# 09_Misc.net
KiCad netlist of a schematic drawn in Altium Designer
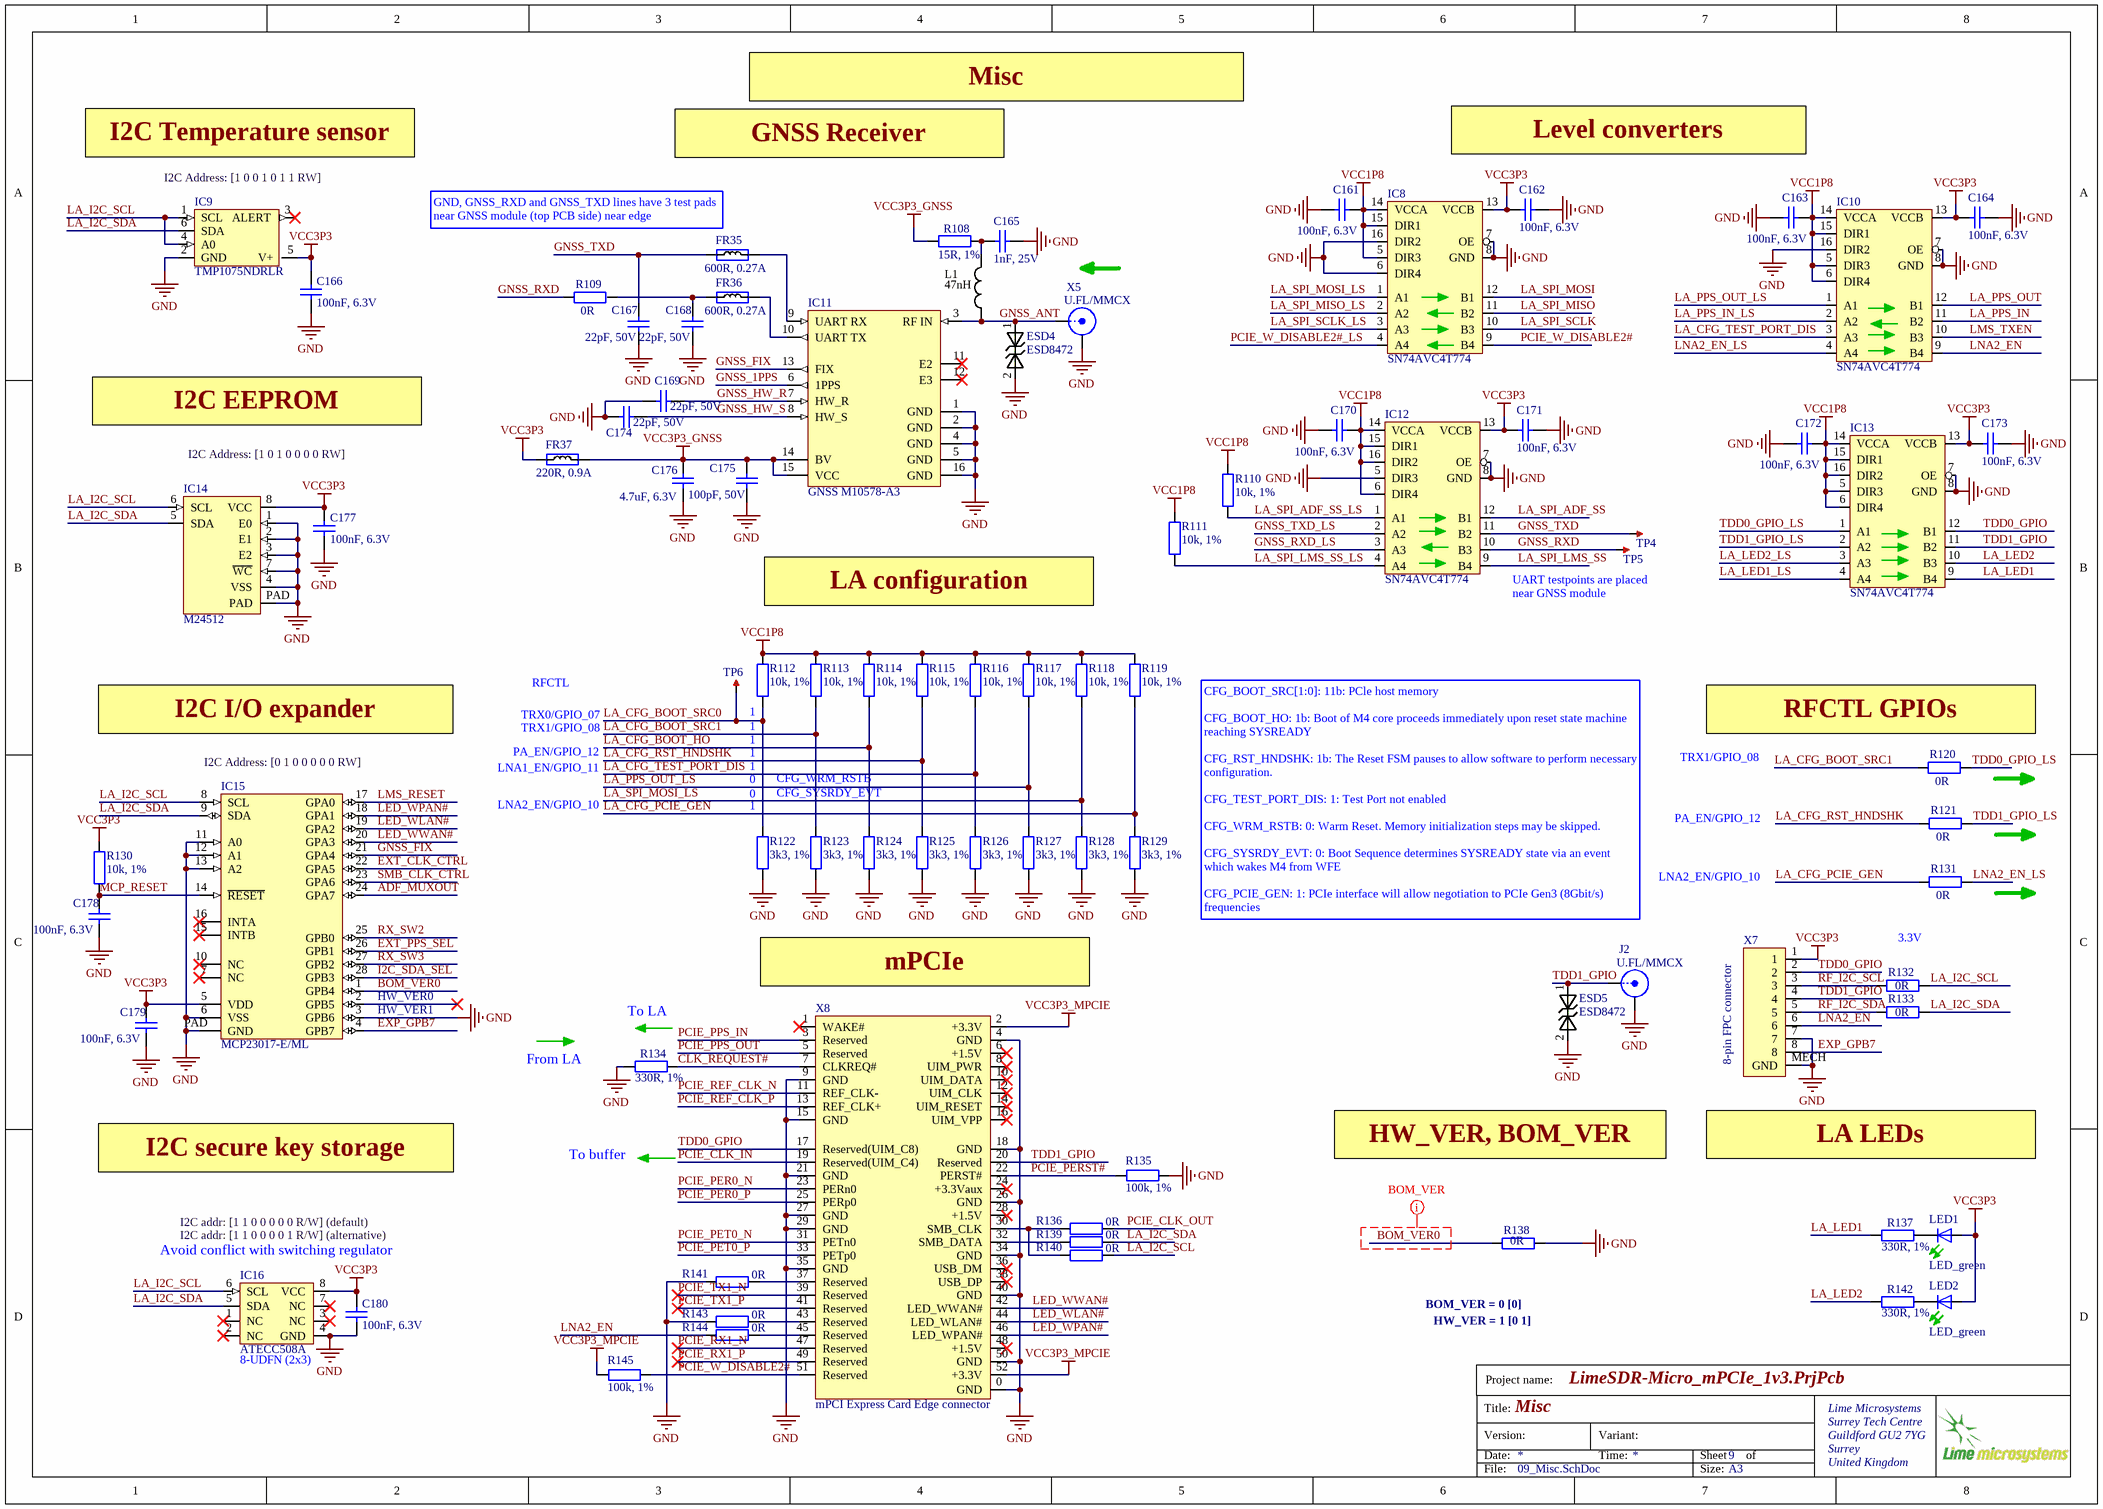
[diagram p0: 09_Misc.SchDoc]

(export (version "E")
  (design (tool "Eeschema 10.0.6"))
  (components
    (comp (ref "C161")
      (value "100nF, 6.3V")
      (footprint "CAP0201")
      (fields (field (name "MANUFACTURER") "Samsung") (field (name "TOLERANCE") "20%"))
      (libsource (lib "LimeMicroAltiumLib_schLib") (part "Cap_0402"))
    )
    (comp (ref "C162")
      (value "100nF, 6.3V")
      (footprint "CAP0201")
      (fields (field (name "MANUFACTURER") "Samsung") (field (name "TOLERANCE") "20%"))
      (libsource (lib "LimeMicroAltiumLib_schLib") (part "Cap_0402"))
    )
    (comp (ref "C163")
      (value "100nF, 6.3V")
      (footprint "CAP0201")
      (fields (field (name "MANUFACTURER") "Samsung") (field (name "TOLERANCE") "20%"))
      (libsource (lib "LimeMicroAltiumLib_schLib") (part "Cap_0402"))
    )
    (comp (ref "C164")
      (value "100nF, 6.3V")
      (footprint "CAP0201")
      (fields (field (name "MANUFACTURER") "Samsung") (field (name "TOLERANCE") "20%"))
      (libsource (lib "LimeMicroAltiumLib_schLib") (part "Cap_0402"))
    )
    (comp (ref "C165")
      (value "1nF, 25V")
      (footprint "CAP0201")
      (fields (field (name "TOLERANCE") "±10%") (field (name "MANUFACTURER") "TDK Corporation"))
      (libsource (lib "LimeMicroAltiumLib_schLib") (part "Cap_0402"))
    )
    (comp (ref "C166")
      (value "100nF, 6.3V")
      (footprint "CAP0201")
      (fields (field (name "MANUFACTURER") "Samsung") (field (name "TOLERANCE") "20%"))
      (libsource (lib "LimeMicroAltiumLib_schLib") (part "Cap_0402"))
    )
    (comp (ref "C167")
      (value "22pF, 50V")
      (footprint "CAP0201")
      (fields
        (field (name "MANUFACTURER") "Murata")
        (field (name "TOLERANCE") "5%")
        (field (name "VOLTAGE") "50V")
      )
      (libsource (lib "LimeMicroAltiumLib_schLib") (part "Cap_0402"))
    )
    (comp (ref "C168")
      (value "22pF, 50V")
      (footprint "CAP0201")
      (fields
        (field (name "MANUFACTURER") "Murata")
        (field (name "TOLERANCE") "5%")
        (field (name "VOLTAGE") "50V")
      )
      (libsource (lib "LimeMicroAltiumLib_schLib") (part "Cap_0402"))
    )
    (comp (ref "C169")
      (value "22pF, 50V")
      (footprint "CAP0201")
      (fields
        (field (name "MANUFACTURER") "Murata")
        (field (name "TOLERANCE") "5%")
        (field (name "VOLTAGE") "50V")
      )
      (libsource (lib "LimeMicroAltiumLib_schLib") (part "Cap_0402"))
    )
    (comp (ref "C170")
      (value "100nF, 6.3V")
      (footprint "CAP0201")
      (fields (field (name "MANUFACTURER") "Samsung") (field (name "TOLERANCE") "20%"))
      (libsource (lib "LimeMicroAltiumLib_schLib") (part "Cap_0402"))
    )
    (comp (ref "C171")
      (value "100nF, 6.3V")
      (footprint "CAP0201")
      (fields (field (name "MANUFACTURER") "Samsung") (field (name "TOLERANCE") "20%"))
      (libsource (lib "LimeMicroAltiumLib_schLib") (part "Cap_0402"))
    )
    (comp (ref "C172")
      (value "100nF, 6.3V")
      (footprint "CAP0201")
      (fields (field (name "MANUFACTURER") "Samsung") (field (name "TOLERANCE") "20%"))
      (libsource (lib "LimeMicroAltiumLib_schLib") (part "Cap_0402"))
    )
    (comp (ref "C173")
      (value "100nF, 6.3V")
      (footprint "CAP0201")
      (fields (field (name "MANUFACTURER") "Samsung") (field (name "TOLERANCE") "20%"))
      (libsource (lib "LimeMicroAltiumLib_schLib") (part "Cap_0402"))
    )
    (comp (ref "C174")
      (value "22pF, 50V")
      (footprint "CAP0201")
      (fields
        (field (name "MANUFACTURER") "Murata")
        (field (name "TOLERANCE") "5%")
        (field (name "VOLTAGE") "50V")
      )
      (libsource (lib "LimeMicroAltiumLib_schLib") (part "Cap_0402"))
    )
    (comp (ref "C175")
      (value "100pF, 50V")
      (footprint "CAP0201")
      (fields
        (field (name "MANUFACTURER") "TDK")
        (field (name "TOLERANCE") "5%")
        (field (name "VOLTAGE") "50V")
      )
      (libsource (lib "LimeMicroAltiumLib_schLib") (part "Cap_0402"))
    )
    (comp (ref "C176")
      (value "4.7uF, 6.3V")
      (footprint "CAP0402")
      (fields
        (field (name "MANUFACTURER") "Murata Electronics North America")
        (field (name "TOLERANCE") "±20%")
      )
      (libsource (lib "LimeMicroAltiumLib_schLib") (part "Cap_0402"))
    )
    (comp (ref "C177")
      (value "100nF, 6.3V")
      (footprint "CAP0201")
      (fields (field (name "MANUFACTURER") "Samsung") (field (name "TOLERANCE") "20%"))
      (libsource (lib "LimeMicroAltiumLib_schLib") (part "Cap_0402"))
    )
    (comp (ref "C178")
      (value "100nF, 6.3V")
      (footprint "CAP0201")
      (fields (field (name "MANUFACTURER") "Samsung") (field (name "TOLERANCE") "20%"))
      (libsource (lib "LimeMicroAltiumLib_schLib") (part "Cap_0402"))
    )
    (comp (ref "C179")
      (value "100nF, 6.3V")
      (footprint "CAP0201")
      (fields (field (name "MANUFACTURER") "Samsung") (field (name "TOLERANCE") "20%"))
      (libsource (lib "LimeMicroAltiumLib_schLib") (part "Cap_0402"))
    )
    (comp (ref "C180")
      (value "100nF, 6.3V")
      (footprint "CAP0201")
      (fields (field (name "MANUFACTURER") "Samsung") (field (name "TOLERANCE") "20%"))
      (libsource (lib "LimeMicroAltiumLib_schLib") (part "Cap_0402"))
    )
    (comp (ref "ESD4")
      (value "ESD8472")
      (footprint "ESD8472_X3DFN2")
      (fields (field (name "MANUFACTURER") "ON Semiconductor"))
      (libsource (lib "LimeMicroAltiumLib_schLib") (part "ESD8472"))
    )
    (comp (ref "ESD5")
      (value "ESD8472")
      (footprint "ESD8472_X3DFN2")
      (fields (field (name "MANUFACTURER") "ON Semiconductor"))
      (libsource (lib "LimeMicroAltiumLib_schLib") (part "ESD8472"))
    )
    (comp (ref "FR35")
      (value "600R, 0.27A")
      (footprint "RES0201")
      (fields (field (name "MANUFACTURER") "Taiyo Yuden"))
      (libsource (lib "LimeMicroAltiumLib_schLib") (part "Ferrite"))
    )
    (comp (ref "FR36")
      (value "600R, 0.27A")
      (footprint "RES0201")
      (fields (field (name "MANUFACTURER") "Taiyo Yuden"))
      (libsource (lib "LimeMicroAltiumLib_schLib") (part "Ferrite"))
    )
    (comp (ref "FR37")
      (value "220R, 0.9A")
      (footprint "RES0402")
      (fields (field (name "MANUFACTURER") "TDK Corporation"))
      (libsource (lib "LimeFPGAboard_schLib") (part "Ferrite"))
    )
    (comp (ref "IC8")
      (value "SN74AVC4T774")
      (footprint "SN74AVC4T774_v1")
      (fields (field (name "MANUFACTURER") "Texas Instruments"))
      (libsource (lib "LimeMicroAltiumLib") (part "SN74AVC4T774"))
    )
    (comp (ref "IC9")
      (value "TMP1075NDRLR")
      (footprint "TMP1075NDRLR_temperature_sensor_SOT563")
      (fields (field (name "MANUFACTURER") "Texas Instruments"))
      (libsource (lib "LimeMicroAltiumLib_schLib_r04") (part "TMP1075NDRLR_temperature_sensor"))
    )
    (comp (ref "IC10")
      (value "SN74AVC4T774")
      (footprint "SN74AVC4T774_v1")
      (fields (field (name "MANUFACTURER") "Texas Instruments"))
      (libsource (lib "LimeMicroAltiumLib") (part "SN74AVC4T774"))
    )
    (comp (ref "IC11")
      (value "GNSS M10578-A3")
      (footprint "M10578-A3_v2")
      (fields (field (name "MANUFACTURER") "Antenova"))
      (libsource (lib "LimeMicroAltiumLib_schLib_r04") (part "M10578-A3_GPS_GNSS"))
    )
    (comp (ref "IC12")
      (value "SN74AVC4T774")
      (footprint "SN74AVC4T774_v1")
      (fields (field (name "MANUFACTURER") "Texas Instruments"))
      (libsource (lib "LimeMicroAltiumLib") (part "SN74AVC4T774"))
    )
    (comp (ref "IC13")
      (value "SN74AVC4T774")
      (footprint "SN74AVC4T774_v1")
      (fields (field (name "MANUFACTURER") "Texas Instruments"))
      (libsource (lib "LimeMicroAltiumLib") (part "SN74AVC4T774"))
    )
    (comp (ref "IC14")
      (value "M24512")
      (footprint "M24128-DFMC6TG")
      (fields (field (name "MANUFACTURER") "STMicroelectronics"))
      (libsource (lib "LimeMicroAltiumLib_schLib") (part "M24128-DFMC6TG"))
    )
    (comp (ref "IC15")
      (value "MCP23017-E/ML")
      (footprint "MCP23017-E/ML_QFN28")
      (fields (field (name "MANUFACTURER") "Microchip"))
      (libsource (lib "LimeMicroAltiumLib") (part "MCP23017-E/ML_I2C_expander"))
    )
    (comp (ref "IC16")
      (value "ATECC508A")
      (footprint "LimeMicroAltiumLib:ATECC508A_UDFN8_v2")
      (fields (field (name "MANUFACTURER") "Microchip"))
      (libsource (lib "LimeMicroAltiumLib_schLib_r01") (part "ATECC508A_authentication_IC"))
    )
    (comp (ref "J2")
      (value "U.FL/MMCX")
      (footprint "MMCX_UFL_conn_u_v2")
      (description "CONN UMC RCPT STR 50 OHM SMD")
      (fields (field (name "MANUFACTURER") "Molex, LLC"))
      (libsource (lib "LimeMicroAltiumLib_schLib") (part "RF_IF_connector"))
    )
    (comp (ref "L1")
      (value "47nH")
      (footprint "RES0402")
      (fields
        (field (name "MANUFACTURER") "COILCRAFT")
        (field (name "MANUFACTURER PART NUMBER") "0402HP-47NXJLU")
      )
      (libsource (lib "LimeMicroAltiumLib_schLib") (part "Inductor_0603"))
    )
    (comp (ref "LED1")
      (value "LED_green")
      (footprint "LED0201")
      (fields (field (name "MANUFACTURER") "Kingbright"))
      (libsource (lib "LimeFPGAboard_schLib") (part "LED_green"))
    )
    (comp (ref "LED2")
      (value "LED_green")
      (footprint "LED0201")
      (fields (field (name "MANUFACTURER") "Kingbright"))
      (libsource (lib "LimeFPGAboard_schLib") (part "LED_green"))
    )
    (comp (ref "R108")
      (value "15R, 1%")
      (footprint "RES0201")
      (fields (field (name "MANUFACTURER") "Yageo") (field (name "TOLERANCE") "1%"))
      (libsource (lib "LimeFPGAboard_schLib") (part "Res_0402"))
    )
    (comp (ref "R109")
      (value "0R")
      (footprint "RES0201")
      (fields (field (name "MANUFACTURER") "Yageo") (field (name "TOLERANCE") "5%"))
      (libsource (lib "LimeFPGAboard_schLib") (part "Res_0402"))
    )
    (comp (ref "R110")
      (value "10k, 1%")
      (footprint "RES0201")
      (fields (field (name "MANUFACTURER") "Yageo") (field (name "TOLERANCE") "1%"))
      (libsource (lib "LimeFPGAboard_schLib") (part "Res_0402"))
    )
    (comp (ref "R111")
      (value "10k, 1%")
      (footprint "RES0201")
      (fields (field (name "MANUFACTURER") "Yageo") (field (name "TOLERANCE") "1%"))
      (libsource (lib "LimeFPGAboard_schLib") (part "Res_0402"))
    )
    (comp (ref "R112")
      (value "10k, 1%")
      (footprint "RES0201")
      (fields (field (name "MANUFACTURER") "Yageo") (field (name "TOLERANCE") "1%"))
      (libsource (lib "LimeFPGAboard_schLib") (part "Res_0402"))
    )
    (comp (ref "R113")
      (value "10k, 1%")
      (footprint "RES0201")
      (fields (field (name "MANUFACTURER") "Yageo") (field (name "TOLERANCE") "1%"))
      (libsource (lib "LimeFPGAboard_schLib") (part "Res_0402"))
    )
    (comp (ref "R114")
      (value "10k, 1%")
      (footprint "RES0201")
      (fields (field (name "MANUFACTURER") "Yageo") (field (name "TOLERANCE") "1%"))
      (libsource (lib "LimeFPGAboard_schLib") (part "Res_0402"))
    )
    (comp (ref "R115")
      (value "10k, 1%")
      (footprint "RES0201")
      (fields (field (name "MANUFACTURER") "Yageo") (field (name "TOLERANCE") "1%"))
      (libsource (lib "LimeFPGAboard_schLib") (part "Res_0402"))
    )
    (comp (ref "R116")
      (value "10k, 1%")
      (footprint "RES0201")
      (fields (field (name "MANUFACTURER") "Yageo") (field (name "TOLERANCE") "1%"))
      (libsource (lib "LimeFPGAboard_schLib") (part "Res_0402"))
    )
    (comp (ref "R117")
      (value "10k, 1%")
      (footprint "RES0201")
      (fields (field (name "MANUFACTURER") "Yageo") (field (name "TOLERANCE") "1%"))
      (libsource (lib "LimeFPGAboard_schLib") (part "Res_0402"))
    )
    (comp (ref "R118")
      (value "10k, 1%")
      (footprint "RES0201")
      (fields (field (name "MANUFACTURER") "Yageo") (field (name "TOLERANCE") "1%"))
      (libsource (lib "LimeFPGAboard_schLib") (part "Res_0402"))
    )
    (comp (ref "R119")
      (value "10k, 1%")
      (footprint "RES0201")
      (fields (field (name "MANUFACTURER") "Yageo") (field (name "TOLERANCE") "1%"))
      (libsource (lib "LimeFPGAboard_schLib") (part "Res_0402"))
    )
    (comp (ref "R120")
      (value "0R")
      (footprint "RES0201")
      (fields (field (name "MANUFACTURER") "Yageo") (field (name "TOLERANCE") "5%"))
      (libsource (lib "LimeFPGAboard_schLib") (part "Res_0402"))
    )
    (comp (ref "R121")
      (value "0R")
      (footprint "RES0201")
      (fields (field (name "MANUFACTURER") "Yageo") (field (name "TOLERANCE") "5%"))
      (libsource (lib "LimeFPGAboard_schLib") (part "Res_0402"))
    )
    (comp (ref "R122")
      (value "3k3, 1%")
      (footprint "RES0201")
      (fields (field (name "MANUFACTURER") "Yageo") (field (name "TOLERANCE") "1%"))
      (libsource (lib "LimeFPGAboard_schLib") (part "Res_0402"))
    )
    (comp (ref "R123")
      (value "3k3, 1%")
      (footprint "RES0201")
      (fields (field (name "MANUFACTURER") "Yageo") (field (name "TOLERANCE") "1%"))
      (libsource (lib "LimeFPGAboard_schLib") (part "Res_0402"))
    )
    (comp (ref "R124")
      (value "3k3, 1%")
      (footprint "RES0201")
      (fields (field (name "MANUFACTURER") "Yageo") (field (name "TOLERANCE") "1%"))
      (libsource (lib "LimeFPGAboard_schLib") (part "Res_0402"))
    )
    (comp (ref "R125")
      (value "3k3, 1%")
      (footprint "RES0201")
      (fields (field (name "MANUFACTURER") "Yageo") (field (name "TOLERANCE") "1%"))
      (libsource (lib "LimeFPGAboard_schLib") (part "Res_0402"))
    )
    (comp (ref "R126")
      (value "3k3, 1%")
      (footprint "RES0201")
      (fields (field (name "MANUFACTURER") "Yageo") (field (name "TOLERANCE") "1%"))
      (libsource (lib "LimeFPGAboard_schLib") (part "Res_0402"))
    )
    (comp (ref "R127")
      (value "3k3, 1%")
      (footprint "RES0201")
      (fields (field (name "MANUFACTURER") "Yageo") (field (name "TOLERANCE") "1%"))
      (libsource (lib "LimeFPGAboard_schLib") (part "Res_0402"))
    )
    (comp (ref "R128")
      (value "3k3, 1%")
      (footprint "RES0201")
      (fields (field (name "MANUFACTURER") "Yageo") (field (name "TOLERANCE") "1%"))
      (libsource (lib "LimeFPGAboard_schLib") (part "Res_0402"))
    )
    (comp (ref "R129")
      (value "3k3, 1%")
      (footprint "RES0201")
      (fields (field (name "MANUFACTURER") "Yageo") (field (name "TOLERANCE") "1%"))
      (libsource (lib "LimeFPGAboard_schLib") (part "Res_0402"))
    )
    (comp (ref "R130")
      (value "10k, 1%")
      (footprint "RES0201")
      (fields (field (name "MANUFACTURER") "Yageo") (field (name "TOLERANCE") "1%"))
      (libsource (lib "LimeFPGAboard_schLib") (part "Res_0402"))
    )
    (comp (ref "R131")
      (value "0R")
      (footprint "RES0201")
      (fields (field (name "MANUFACTURER") "Yageo") (field (name "TOLERANCE") "5%"))
      (libsource (lib "LimeFPGAboard_schLib") (part "Res_0402"))
    )
    (comp (ref "R132")
      (value "0R")
      (footprint "RES0201")
      (fields (field (name "MANUFACTURER") "Yageo") (field (name "TOLERANCE") "5%"))
      (libsource (lib "LimeFPGAboard_schLib") (part "Res_0402"))
    )
    (comp (ref "R133")
      (value "0R")
      (footprint "RES0201")
      (fields (field (name "MANUFACTURER") "Yageo") (field (name "TOLERANCE") "5%"))
      (libsource (lib "LimeFPGAboard_schLib") (part "Res_0402"))
    )
    (comp (ref "R134")
      (value "330R, 1%")
      (footprint "RES0201")
      (fields (field (name "MANUFACTURER") "Vishay Dale") (field (name "TOLERANCE") "1%"))
      (libsource (lib "LimeFPGAboard_schLib") (part "Res_0402"))
    )
    (comp (ref "R135")
      (value "100k, 1%")
      (footprint "RES0201")
      (fields (field (name "MANUFACTURER") "Yageo") (field (name "TOLERANCE") "1%"))
      (libsource (lib "LimeMicroAltiumLib_schLib") (part "Res_0402"))
    )
    (comp (ref "R136")
      (value "0R")
      (footprint "RES0201")
      (fields (field (name "MANUFACTURER") "Yageo") (field (name "TOLERANCE") "5%"))
      (libsource (lib "LimeFPGAboard_schLib") (part "Res_0402"))
    )
    (comp (ref "R137")
      (value "330R, 1%")
      (footprint "RES0201")
      (fields (field (name "MANUFACTURER") "Vishay Dale") (field (name "TOLERANCE") "1%"))
      (libsource (lib "LimeFPGAboard_schLib") (part "Res_0402"))
    )
    (comp (ref "R138")
      (value "0R")
      (footprint "RES0201")
      (fields (field (name "MANUFACTURER") "Yageo") (field (name "TOLERANCE") "5%"))
      (libsource (lib "LimeFPGAboard_schLib") (part "Res_0402"))
    )
    (comp (ref "R139")
      (value "0R")
      (footprint "RES0201")
      (fields (field (name "MANUFACTURER") "Yageo") (field (name "TOLERANCE") "5%"))
      (libsource (lib "LimeFPGAboard_schLib") (part "Res_0402"))
    )
    (comp (ref "R140")
      (value "0R")
      (footprint "RES0201")
      (fields (field (name "MANUFACTURER") "Yageo") (field (name "TOLERANCE") "5%"))
      (libsource (lib "LimeFPGAboard_schLib") (part "Res_0402"))
    )
    (comp (ref "R141")
      (value "0R")
      (footprint "RES0201")
      (fields (field (name "MANUFACTURER") "Yageo") (field (name "TOLERANCE") "5%"))
      (libsource (lib "LimeFPGAboard_schLib") (part "Res_0402"))
    )
    (comp (ref "R142")
      (value "330R, 1%")
      (footprint "RES0201")
      (fields (field (name "MANUFACTURER") "Vishay Dale") (field (name "TOLERANCE") "1%"))
      (libsource (lib "LimeFPGAboard_schLib") (part "Res_0402"))
    )
    (comp (ref "R143")
      (value "0R")
      (footprint "RES0201")
      (fields (field (name "MANUFACTURER") "Yageo") (field (name "TOLERANCE") "5%"))
      (libsource (lib "LimeFPGAboard_schLib") (part "Res_0402"))
    )
    (comp (ref "R144")
      (value "0R")
      (footprint "RES0201")
      (fields (field (name "MANUFACTURER") "Yageo") (field (name "TOLERANCE") "5%"))
      (libsource (lib "LimeFPGAboard_schLib") (part "Res_0402"))
    )
    (comp (ref "R145")
      (value "100k, 1%")
      (footprint "RES0201")
      (fields (field (name "MANUFACTURER") "Yageo") (field (name "TOLERANCE") "1%"))
      (libsource (lib "LimeMicroAltiumLib_schLib") (part "Res_0402"))
    )
    (comp (ref "TP4")
      (value "TESTPOINT_PAD")
      (footprint "TP_PAD_1MM")
      (description "Test Point PCB mount Miniature White")
      (libsource (lib "LimeMicroAltiumLib_schLib_r04") (part "TESTPOINT_PAD"))
    )
    (comp (ref "TP5")
      (value "TESTPOINT_PAD")
      (footprint "TP_PAD_1MM")
      (description "Test Point PCB mount Miniature White")
      (libsource (lib "LimeMicroAltiumLib_schLib_r04") (part "TESTPOINT_PAD"))
    )
    (comp (ref "TP6")
      (value "TESTPOINT_PAD")
      (footprint "TP_PAD_1MM")
      (description "Test Point PCB mount Miniature White")
      (libsource (lib "LimeMicroAltiumLib_schLib_r04") (part "TESTPOINT_PAD"))
    )
    (comp (ref "X5")
      (value "U.FL/MMCX")
      (footprint "MMCX_UFL_conn_u_v2")
      (description "CONN UMC RCPT STR 50 OHM SMD")
      (fields (field (name "MANUFACTURER") "Molex, LLC"))
      (libsource (lib "LimeMicroAltiumLib_schLib") (part "RF_IF_connector"))
    )
    (comp (ref "X7")
      (value "8-pin FPC connector")
      (footprint "503480-0800_8PIN_FPC_CONN")
      (fields (field (name "MANUFACTURER") "Molex"))
      (libsource (lib "LimeMicroAltiumLib_schLib_r04") (part "503480-0800_8PIN_FPC_CONN"))
    )
    (comp (ref "X8")
      (value "mPCI Express Card Edge connector")
      (footprint "PCIe_MiniCard")
      (description "PCIe MiniCard full or half size")
      (libsource (lib "LimeMicroAltiumLib_schLib_r04") (part "PCIe_MiniCard_fingers"))
    )
  )
  (nets
    (net (code "1") (name "/ADF_MUXOUT") (class "Default")
      (node (ref "IC15") (pin "24") (pinfunction "GPA7_24") (pintype "bidirectional"))
    )
    (net (code "2") (name "/BOM_VER0") (class "Default")
      (node (ref "IC15") (pin "1") (pinfunction "GPB4_1") (pintype "bidirectional"))
      (node (ref "R138") (pin "1") (pinfunction "1_1") (pintype "passive"))
    )
    (net (code "3") (name "/CLK_REQUEST#") (class "Default")
      (node (ref "R134") (pin "1") (pinfunction "1_1") (pintype "passive"))
      (node (ref "X8") (pin "7") (pinfunction "CLKREQ#_7") (pintype "passive"))
    )
    (net (code "4") (name "/EXP_GPB7") (class "Default")
      (node (ref "IC15") (pin "4") (pinfunction "GPB7_4") (pintype "bidirectional"))
      (node (ref "X7") (pin "8") (pinfunction "8_8") (pintype "passive"))
    )
    (net (code "5") (name "/EXT_CLK_CTRL") (class "Default")
      (node (ref "IC15") (pin "22") (pinfunction "GPA5_22") (pintype "bidirectional"))
    )
    (net (code "6") (name "/EXT_PPS_SEL") (class "Default")
      (node (ref "IC15") (pin "26") (pinfunction "GPB1_26") (pintype "bidirectional"))
    )
    (net (code "7") (name "/GNSS_1PPS") (class "Default")
      (node (ref "IC11") (pin "6") (pinfunction "1PPS_6") (pintype "output"))
    )
    (net (code "8") (name "/GNSS_ANT") (class "Default")
      (node (ref "ESD4") (pin "1") (pinfunction "1_1") (pintype "passive"))
      (node (ref "IC11") (pin "3") (pinfunction "RF_IN_3") (pintype "input"))
      (node (ref "L1") (pin "1") (pinfunction "1_1") (pintype "passive"))
      (node (ref "X5") (pin "1") (pinfunction "X_1") (pintype "passive"))
    )
    (net (code "9") (name "/GNSS_FIX") (class "Default")
      (node (ref "IC11") (pin "13") (pinfunction "FIX_13") (pintype "output"))
      (node (ref "IC15") (pin "21") (pinfunction "GPA4_21") (pintype "bidirectional"))
    )
    (net (code "10") (name "/GNSS_HW_R") (class "Default")
      (node (ref "C169") (pin "1") (pinfunction "1_1") (pintype "passive"))
      (node (ref "IC11") (pin "7") (pinfunction "HW_R_7") (pintype "input"))
    )
    (net (code "11") (name "/GNSS_HW_S") (class "Default")
      (node (ref "C174") (pin "1") (pinfunction "1_1") (pintype "passive"))
      (node (ref "IC11") (pin "8") (pinfunction "HW_S_8") (pintype "input"))
    )
    (net (code "12") (name "/GNSS_RXD") (class "Default")
      (node (ref "IC12") (pin "10") (pinfunction "B3_10") (pintype "passive"))
      (node (ref "R109") (pin "1") (pinfunction "1_1") (pintype "passive"))
      (node (ref "TP5") (pin "1") (pintype "passive"))
    )
    (net (code "13") (name "/GNSS_RXD_LS") (class "Default")
      (node (ref "IC12") (pin "3") (pinfunction "A3_3") (pintype "passive"))
    )
    (net (code "14") (name "/GNSS_TXD") (class "Default")
      (node (ref "C167") (pin "1") (pinfunction "1_1") (pintype "passive"))
      (node (ref "FR35") (pin "1") (pinfunction "1_1") (pintype "passive"))
      (node (ref "IC12") (pin "11") (pinfunction "B2_11") (pintype "passive"))
      (node (ref "TP4") (pin "1") (pintype "passive"))
    )
    (net (code "15") (name "/GNSS_TXD_LS") (class "Default")
      (node (ref "IC12") (pin "2") (pinfunction "A2_2") (pintype "passive"))
    )
    (net (code "16") (name "/I2C_SDA_SEL") (class "Default")
      (node (ref "IC15") (pin "28") (pinfunction "GPB3_28") (pintype "bidirectional"))
    )
    (net (code "17") (name "/LA_CFG_BOOT_HO") (class "Default")
      (node (ref "R114") (pin "2") (pinfunction "2_2") (pintype "passive"))
      (node (ref "R124") (pin "1") (pinfunction "1_1") (pintype "passive"))
    )
    (net (code "18") (name "/LA_CFG_BOOT_SRC0") (class "Default")
      (node (ref "R112") (pin "2") (pinfunction "2_2") (pintype "passive"))
      (node (ref "R122") (pin "1") (pinfunction "1_1") (pintype "passive"))
      (node (ref "TP6") (pin "1") (pintype "passive"))
    )
    (net (code "19") (name "/LA_CFG_BOOT_SRC1") (class "Default")
      (node (ref "R113") (pin "2") (pinfunction "2_2") (pintype "passive"))
      (node (ref "R120") (pin "1") (pinfunction "1_1") (pintype "passive"))
      (node (ref "R123") (pin "1") (pinfunction "1_1") (pintype "passive"))
    )
    (net (code "20") (name "/LA_CFG_PCIE_GEN") (class "Default")
      (node (ref "R119") (pin "2") (pinfunction "2_2") (pintype "passive"))
      (node (ref "R129") (pin "1") (pinfunction "1_1") (pintype "passive"))
      (node (ref "R131") (pin "1") (pinfunction "1_1") (pintype "passive"))
    )
    (net (code "21") (name "/LA_CFG_RST_HNDSHK") (class "Default")
      (node (ref "R115") (pin "2") (pinfunction "2_2") (pintype "passive"))
      (node (ref "R121") (pin "1") (pinfunction "1_1") (pintype "passive"))
      (node (ref "R125") (pin "1") (pinfunction "1_1") (pintype "passive"))
    )
    (net (code "22") (name "/LA_CFG_TEST_PORT_DIS") (class "Default")
      (node (ref "IC10") (pin "3") (pinfunction "A3_3") (pintype "passive"))
      (node (ref "R116") (pin "2") (pinfunction "2_2") (pintype "passive"))
      (node (ref "R126") (pin "1") (pinfunction "1_1") (pintype "passive"))
    )
    (net (code "23") (name "/LA_I2C_SCL") (class "Default")
      (node (ref "IC14") (pin "6") (pinfunction "SCL_6") (pintype "input"))
      (node (ref "IC15") (pin "8") (pinfunction "SCL_8") (pintype "input"))
      (node (ref "IC16") (pin "6") (pinfunction "SCL_6") (pintype "input"))
      (node (ref "IC9") (pin "1") (pinfunction "SCL_1") (pintype "input"))
      (node (ref "IC9") (pin "4") (pinfunction "A0_4") (pintype "input"))
      (node (ref "R132") (pin "2") (pinfunction "2_2") (pintype "passive"))
      (node (ref "R140") (pin "2") (pinfunction "2_2") (pintype "passive"))
    )
    (net (code "24") (name "/LA_I2C_SDA") (class "Default")
      (node (ref "IC14") (pin "5") (pinfunction "SDA_5") (pintype "bidirectional"))
      (node (ref "IC15") (pin "9") (pinfunction "SDA_9") (pintype "bidirectional"))
      (node (ref "IC16") (pin "5") (pinfunction "SDA_5") (pintype "bidirectional"))
      (node (ref "IC9") (pin "6") (pinfunction "SDA_6") (pintype "bidirectional"))
      (node (ref "R133") (pin "2") (pinfunction "2_2") (pintype "passive"))
      (node (ref "R139") (pin "2") (pinfunction "2_2") (pintype "passive"))
    )
    (net (code "25") (name "/LA_LED1") (class "Default")
      (node (ref "IC13") (pin "9") (pinfunction "B4_9") (pintype "passive"))
      (node (ref "R137") (pin "2") (pinfunction "2_2") (pintype "passive"))
    )
    (net (code "26") (name "/LA_LED1_LS") (class "Default")
      (node (ref "IC13") (pin "4") (pinfunction "A4_4") (pintype "passive"))
    )
    (net (code "27") (name "/LA_LED2") (class "Default")
      (node (ref "IC13") (pin "10") (pinfunction "B3_10") (pintype "passive"))
      (node (ref "R142") (pin "2") (pinfunction "2_2") (pintype "passive"))
    )
    (net (code "28") (name "/LA_LED2_LS") (class "Default")
      (node (ref "IC13") (pin "3") (pinfunction "A3_3") (pintype "passive"))
    )
    (net (code "29") (name "/LA_PPS_IN") (class "Default")
      (node (ref "IC10") (pin "11") (pinfunction "B2_11") (pintype "passive"))
    )
    (net (code "30") (name "/LA_PPS_IN_LS") (class "Default")
      (node (ref "IC10") (pin "2") (pinfunction "A2_2") (pintype "passive"))
    )
    (net (code "31") (name "/LA_PPS_OUT") (class "Default")
      (node (ref "IC10") (pin "12") (pinfunction "B1_12") (pintype "passive"))
    )
    (net (code "32") (name "/LA_PPS_OUT_LS") (class "Default")
      (node (ref "IC10") (pin "1") (pinfunction "A1_1") (pintype "passive"))
      (node (ref "R117") (pin "2") (pinfunction "2_2") (pintype "passive"))
      (node (ref "R127") (pin "1") (pinfunction "1_1") (pintype "passive"))
    )
    (net (code "33") (name "/LA_SPI_ADF_SS") (class "Default")
      (node (ref "IC12") (pin "12") (pinfunction "B1_12") (pintype "passive"))
    )
    (net (code "34") (name "/LA_SPI_ADF_SS_LS") (class "Default")
      (node (ref "IC12") (pin "1") (pinfunction "A1_1") (pintype "passive"))
      (node (ref "R110") (pin "2") (pinfunction "2_2") (pintype "passive"))
    )
    (net (code "35") (name "/LA_SPI_LMS_SS") (class "Default")
      (node (ref "IC12") (pin "9") (pinfunction "B4_9") (pintype "passive"))
    )
    (net (code "36") (name "/LA_SPI_LMS_SS_LS") (class "Default")
      (node (ref "IC12") (pin "4") (pinfunction "A4_4") (pintype "passive"))
      (node (ref "R111") (pin "2") (pinfunction "2_2") (pintype "passive"))
    )
    (net (code "37") (name "/LA_SPI_MISO") (class "Default")
      (node (ref "IC8") (pin "11") (pinfunction "B2_11") (pintype "passive"))
    )
    (net (code "38") (name "/LA_SPI_MISO_LS") (class "Default")
      (node (ref "IC8") (pin "2") (pinfunction "A2_2") (pintype "passive"))
    )
    (net (code "39") (name "/LA_SPI_MOSI") (class "Default")
      (node (ref "IC8") (pin "12") (pinfunction "B1_12") (pintype "passive"))
    )
    (net (code "40") (name "/LA_SPI_MOSI_LS") (class "Default")
      (node (ref "IC8") (pin "1") (pinfunction "A1_1") (pintype "passive"))
      (node (ref "R118") (pin "2") (pinfunction "2_2") (pintype "passive"))
      (node (ref "R128") (pin "1") (pinfunction "1_1") (pintype "passive"))
    )
    (net (code "41") (name "/LA_SPI_SCLK") (class "Default")
      (node (ref "IC8") (pin "10") (pinfunction "B3_10") (pintype "passive"))
    )
    (net (code "42") (name "/LA_SPI_SCLK_LS") (class "Default")
      (node (ref "IC8") (pin "3") (pinfunction "A3_3") (pintype "passive"))
    )
    (net (code "43") (name "/LED_WLAN#") (class "Default")
      (node (ref "IC15") (pin "19") (pinfunction "GPA2_19") (pintype "bidirectional"))
      (node (ref "X8") (pin "44") (pinfunction "LED_WLAN#_44") (pintype "passive"))
    )
    (net (code "44") (name "/LED_WPAN#") (class "Default")
      (node (ref "IC15") (pin "18") (pinfunction "GPA1_18") (pintype "bidirectional"))
      (node (ref "X8") (pin "46") (pinfunction "LED_WPAN#_46") (pintype "passive"))
    )
    (net (code "45") (name "/LED_WWAN#") (class "Default")
      (node (ref "IC15") (pin "20") (pinfunction "GPA3_20") (pintype "bidirectional"))
      (node (ref "X8") (pin "42") (pinfunction "LED_WWAN#_42") (pintype "passive"))
    )
    (net (code "46") (name "/LMS_RESET") (class "Default")
      (node (ref "IC15") (pin "17") (pinfunction "GPA0_17") (pintype "bidirectional"))
    )
    (net (code "47") (name "/LMS_TXEN") (class "Default")
      (node (ref "IC10") (pin "10") (pinfunction "B3_10") (pintype "passive"))
    )
    (net (code "48") (name "/LNA2_EN") (class "Default")
      (node (ref "IC10") (pin "9") (pinfunction "B4_9") (pintype "passive"))
      (node (ref "R144") (pin "1") (pinfunction "1_1") (pintype "passive"))
      (node (ref "X7") (pin "6") (pinfunction "6_6") (pintype "passive"))
    )
    (net (code "49") (name "/LNA2_EN_LS") (class "Default")
      (node (ref "IC10") (pin "4") (pinfunction "A4_4") (pintype "passive"))
      (node (ref "R131") (pin "2") (pinfunction "2_2") (pintype "passive"))
    )
    (net (code "50") (name "/MCP_RESET") (class "Default")
      (node (ref "C178") (pin "1") (pinfunction "1_1") (pintype "passive"))
      (node (ref "IC15") (pin "14") (pinfunction "~{RESET}_14") (pintype "input"))
      (node (ref "R130") (pin "2") (pinfunction "2_2") (pintype "passive"))
    )
    (net (code "51") (name "/PCIE_CLK_IN") (class "Default")
      (node (ref "X8") (pin "19") (pinfunction "Reserved(UIM_C4)_19") (pintype "passive"))
    )
    (net (code "52") (name "/PCIE_CLK_OUT") (class "Default")
      (node (ref "R136") (pin "2") (pinfunction "2_2") (pintype "passive"))
    )
    (net (code "53") (name "/PCIE_PER0_N") (class "Default")
      (node (ref "X8") (pin "23") (pinfunction "PERn0_23") (pintype "passive"))
    )
    (net (code "54") (name "/PCIE_PER0_P") (class "Default")
      (node (ref "X8") (pin "25") (pinfunction "PERp0_25") (pintype "passive"))
    )
    (net (code "55") (name "/PCIE_PERST#") (class "Default")
      (node (ref "R135") (pin "2") (pinfunction "2_2") (pintype "passive"))
      (node (ref "X8") (pin "22") (pinfunction "PERST#_22") (pintype "passive"))
    )
    (net (code "56") (name "/PCIE_PET0_N") (class "Default")
      (node (ref "X8") (pin "31") (pinfunction "PETn0_31") (pintype "passive"))
    )
    (net (code "57") (name "/PCIE_PET0_P") (class "Default")
      (node (ref "X8") (pin "33") (pinfunction "PETp0_33") (pintype "passive"))
    )
    (net (code "58") (name "/PCIE_PPS_IN") (class "Default")
      (node (ref "X8") (pin "3") (pinfunction "Reserved_3") (pintype "passive"))
    )
    (net (code "59") (name "/PCIE_PPS_OUT") (class "Default")
      (node (ref "X8") (pin "5") (pinfunction "Reserved_5") (pintype "passive"))
    )
    (net (code "60") (name "/PCIE_REF_CLK_N") (class "Default")
      (node (ref "X8") (pin "11") (pinfunction "REF_CLK-_11") (pintype "passive"))
    )
    (net (code "61") (name "/PCIE_REF_CLK_P") (class "Default")
      (node (ref "X8") (pin "13") (pinfunction "REF_CLK+_13") (pintype "passive"))
    )
    (net (code "62") (name "/PCIE_RX1_N") (class "Default")
      (node (ref "X8") (pin "47") (pinfunction "Reserved_47") (pintype "passive+no_connect"))
    )
    (net (code "63") (name "/PCIE_RX1_P") (class "Default")
      (node (ref "X8") (pin "49") (pinfunction "Reserved_49") (pintype "passive+no_connect"))
    )
    (net (code "64") (name "/PCIE_TX1_N") (class "Default")
      (node (ref "X8") (pin "39") (pinfunction "Reserved_39") (pintype "passive+no_connect"))
    )
    (net (code "65") (name "/PCIE_TX1_P") (class "Default")
      (node (ref "X8") (pin "41") (pinfunction "Reserved_41") (pintype "passive+no_connect"))
    )
    (net (code "66") (name "/PCIE_W_DISABLE2#") (class "Default")
      (node (ref "IC8") (pin "9") (pinfunction "B4_9") (pintype "passive"))
      (node (ref "R145") (pin "1") (pinfunction "1_1") (pintype "passive"))
      (node (ref "X8") (pin "51") (pinfunction "Reserved_51") (pintype "passive"))
    )
    (net (code "67") (name "/PCIE_W_DISABLE2#_LS") (class "Default")
      (node (ref "IC8") (pin "4") (pinfunction "A4_4") (pintype "passive"))
    )
    (net (code "68") (name "/RF_I2C_SCL") (class "Default")
      (node (ref "R132") (pin "1") (pinfunction "1_1") (pintype "passive"))
      (node (ref "X7") (pin "3") (pinfunction "3_3") (pintype "passive"))
    )
    (net (code "69") (name "/RF_I2C_SDA") (class "Default")
      (node (ref "R133") (pin "1") (pinfunction "1_1") (pintype "passive"))
      (node (ref "X7") (pin "5") (pinfunction "5_5") (pintype "passive"))
    )
    (net (code "70") (name "/RX_SW2") (class "Default")
      (node (ref "IC15") (pin "25") (pinfunction "GPB0_25") (pintype "bidirectional"))
    )
    (net (code "71") (name "/RX_SW3") (class "Default")
      (node (ref "IC15") (pin "27") (pinfunction "GPB2_27") (pintype "bidirectional"))
    )
    (net (code "72") (name "/SMB_CLK_CTRL") (class "Default")
      (node (ref "IC15") (pin "23") (pinfunction "GPA6_23") (pintype "bidirectional"))
    )
    (net (code "73") (name "/TDD0_GPIO") (class "Default")
      (node (ref "IC13") (pin "12") (pinfunction "B1_12") (pintype "passive"))
      (node (ref "X7") (pin "2") (pinfunction "2_2") (pintype "passive"))
      (node (ref "X8") (pin "17") (pinfunction "Reserved(UIM_C8)_17") (pintype "passive"))
    )
    (net (code "74") (name "/TDD0_GPIO_LS") (class "Default")
      (node (ref "IC13") (pin "1") (pinfunction "A1_1") (pintype "passive"))
      (node (ref "R120") (pin "2") (pinfunction "2_2") (pintype "passive"))
    )
    (net (code "75") (name "/TDD1_GPIO") (class "Default")
      (node (ref "ESD5") (pin "1") (pinfunction "1_1") (pintype "passive"))
      (node (ref "IC13") (pin "11") (pinfunction "B2_11") (pintype "passive"))
      (node (ref "J2") (pin "1") (pinfunction "X_1") (pintype "passive"))
      (node (ref "X7") (pin "4") (pinfunction "4_4") (pintype "passive"))
      (node (ref "X8") (pin "20") (pinfunction "Reserved_20") (pintype "passive"))
    )
    (net (code "76") (name "/TDD1_GPIO_LS") (class "Default")
      (node (ref "IC13") (pin "2") (pinfunction "A2_2") (pintype "passive"))
      (node (ref "R121") (pin "2") (pinfunction "2_2") (pintype "passive"))
    )
    (net (code "77") (name "GND") (class "Default")
      (node (ref "C161") (pin "1") (pinfunction "1_1") (pintype "passive"))
      (node (ref "C162") (pin "2") (pinfunction "2_2") (pintype "passive"))
      (node (ref "C163") (pin "1") (pinfunction "1_1") (pintype "passive"))
      (node (ref "C164") (pin "2") (pinfunction "2_2") (pintype "passive"))
      (node (ref "C165") (pin "2") (pinfunction "2_2") (pintype "passive"))
      (node (ref "C166") (pin "2") (pinfunction "2_2") (pintype "passive"))
      (node (ref "C167") (pin "2") (pinfunction "2_2") (pintype "passive"))
      (node (ref "C168") (pin "2") (pinfunction "2_2") (pintype "passive"))
      (node (ref "C169") (pin "2") (pinfunction "2_2") (pintype "passive"))
      (node (ref "C170") (pin "1") (pinfunction "1_1") (pintype "passive"))
      (node (ref "C171") (pin "2") (pinfunction "2_2") (pintype "passive"))
      (node (ref "C172") (pin "1") (pinfunction "1_1") (pintype "passive"))
      (node (ref "C173") (pin "2") (pinfunction "2_2") (pintype "passive"))
      (node (ref "C174") (pin "2") (pinfunction "2_2") (pintype "passive"))
      (node (ref "C175") (pin "1") (pinfunction "1_1") (pintype "passive"))
      (node (ref "C176") (pin "1") (pinfunction "1_1") (pintype "passive"))
      (node (ref "C177") (pin "2") (pinfunction "2_2") (pintype "passive"))
      (node (ref "C178") (pin "2") (pinfunction "2_2") (pintype "passive"))
      (node (ref "C179") (pin "2") (pinfunction "2_2") (pintype "passive"))
      (node (ref "C180") (pin "2") (pinfunction "2_2") (pintype "passive"))
      (node (ref "ESD4") (pin "2") (pinfunction "2_2") (pintype "passive"))
      (node (ref "ESD5") (pin "2") (pinfunction "2_2") (pintype "passive"))
      (node (ref "IC10") (pin "16") (pinfunction "DIR2_16") (pintype "passive"))
      (node (ref "IC10") (pin "7") (pinfunction "OE_7") (pintype "passive"))
      (node (ref "IC10") (pin "8") (pinfunction "GND_8") (pintype "passive"))
      (node (ref "IC11") (pin "1") (pinfunction "GND_1") (pintype "passive"))
      (node (ref "IC11") (pin "16") (pinfunction "GND_16") (pintype "passive"))
      (node (ref "IC11") (pin "2") (pinfunction "GND_2") (pintype "passive"))
      (node (ref "IC11") (pin "4") (pinfunction "GND_4") (pintype "passive"))
      (node (ref "IC11") (pin "5") (pinfunction "GND_5") (pintype "passive"))
      (node (ref "IC12") (pin "5") (pinfunction "DIR3_5") (pintype "passive"))
      (node (ref "IC12") (pin "7") (pinfunction "OE_7") (pintype "passive"))
      (node (ref "IC12") (pin "8") (pinfunction "GND_8") (pintype "passive"))
      (node (ref "IC13") (pin "7") (pinfunction "OE_7") (pintype "passive"))
      (node (ref "IC13") (pin "8") (pinfunction "GND_8") (pintype "passive"))
      (node (ref "IC14") (pin "1") (pinfunction "E0_1") (pintype "input"))
      (node (ref "IC14") (pin "2") (pinfunction "E1_2") (pintype "input"))
      (node (ref "IC14") (pin "3") (pinfunction "E2_3") (pintype "input"))
      (node (ref "IC14") (pin "4") (pinfunction "VSS_4") (pintype "power_in"))
      (node (ref "IC14") (pin "7") (pinfunction "~{WC}_7") (pintype "input"))
      (node (ref "IC14") (pin "PAD") (pinfunction "PAD_PAD") (pintype "power_in"))
      (node (ref "IC15") (pin "11") (pinfunction "A0_11") (pintype "input"))
      (node (ref "IC15") (pin "12") (pinfunction "A1_12") (pintype "input"))
      (node (ref "IC15") (pin "13") (pinfunction "A2_13") (pintype "input"))
      (node (ref "IC15") (pin "3") (pinfunction "GPB6_3") (pintype "bidirectional"))
      (node (ref "IC15") (pin "6") (pinfunction "VSS_6") (pintype "power_in"))
      (node (ref "IC15") (pin "PAD") (pinfunction "GND_PAD") (pintype "passive"))
      (node (ref "IC16") (pin "4") (pinfunction "GND_4") (pintype "passive"))
      (node (ref "IC8") (pin "16") (pinfunction "DIR2_16") (pintype "passive"))
      (node (ref "IC8") (pin "6") (pinfunction "DIR4_6") (pintype "passive"))
      (node (ref "IC8") (pin "7") (pinfunction "OE_7") (pintype "passive"))
      (node (ref "IC8") (pin "8") (pinfunction "GND_8") (pintype "passive"))
      (node (ref "IC9") (pin "2") (pinfunction "GND_2") (pintype "passive"))
      (node (ref "J2") (pin "2") (pinfunction "Y_2") (pintype "passive"))
      (node (ref "R122") (pin "2") (pinfunction "2_2") (pintype "passive"))
      (node (ref "R123") (pin "2") (pinfunction "2_2") (pintype "passive"))
      (node (ref "R124") (pin "2") (pinfunction "2_2") (pintype "passive"))
      (node (ref "R125") (pin "2") (pinfunction "2_2") (pintype "passive"))
      (node (ref "R126") (pin "2") (pinfunction "2_2") (pintype "passive"))
      (node (ref "R127") (pin "2") (pinfunction "2_2") (pintype "passive"))
      (node (ref "R128") (pin "2") (pinfunction "2_2") (pintype "passive"))
      (node (ref "R129") (pin "2") (pinfunction "2_2") (pintype "passive"))
      (node (ref "R134") (pin "2") (pinfunction "2_2") (pintype "passive"))
      (node (ref "R135") (pin "1") (pinfunction "1_1") (pintype "passive"))
      (node (ref "R138") (pin "2") (pinfunction "2_2") (pintype "passive"))
      (node (ref "R141") (pin "1") (pinfunction "1_1") (pintype "passive"))
      (node (ref "R143") (pin "1") (pinfunction "1_1") (pintype "passive"))
      (node (ref "X5") (pin "2") (pinfunction "Y_2") (pintype "passive"))
      (node (ref "X7") (pin "7") (pinfunction "7_7") (pintype "passive"))
      (node (ref "X7") (pin "MECH") (pinfunction "GND_MECH") (pintype "passive"))
      (node (ref "X8") (pin "0") (pinfunction "GND_0") (pintype "passive"))
      (node (ref "X8") (pin "15") (pinfunction "GND_15") (pintype "passive"))
      (node (ref "X8") (pin "18") (pinfunction "GND_18") (pintype "passive"))
      (node (ref "X8") (pin "21") (pinfunction "GND_21") (pintype "passive"))
      (node (ref "X8") (pin "26") (pinfunction "GND_26") (pintype "passive"))
      (node (ref "X8") (pin "27") (pinfunction "GND_27") (pintype "passive"))
      (node (ref "X8") (pin "29") (pinfunction "GND_29") (pintype "passive"))
      (node (ref "X8") (pin "34") (pinfunction "GND_34") (pintype "passive"))
      (node (ref "X8") (pin "35") (pinfunction "GND_35") (pintype "passive"))
      (node (ref "X8") (pin "4") (pinfunction "GND_4") (pintype "passive"))
      (node (ref "X8") (pin "40") (pinfunction "GND_40") (pintype "passive"))
      (node (ref "X8") (pin "50") (pinfunction "GND_50") (pintype "passive"))
      (node (ref "X8") (pin "9") (pinfunction "GND_9") (pintype "passive"))
    )
    (net (code "78") (name "Net-(C165-Pad1)") (class "Default")
      (node (ref "C165") (pin "1") (pinfunction "1_1") (pintype "passive"))
      (node (ref "L1") (pin "2") (pinfunction "2_2") (pintype "passive"))
      (node (ref "R108") (pin "1") (pinfunction "1_1") (pintype "passive"))
    )
    (net (code "79") (name "Net-(C168-Pad1)") (class "Default")
      (node (ref "C168") (pin "1") (pinfunction "1_1") (pintype "passive"))
      (node (ref "FR36") (pin "1") (pinfunction "1_1") (pintype "passive"))
      (node (ref "R109") (pin "2") (pinfunction "2_2") (pintype "passive"))
    )
    (net (code "80") (name "Net-(IC11-UART_RX)") (class "Default")
      (node (ref "FR35") (pin "2") (pinfunction "2_2") (pintype "passive"))
      (node (ref "IC11") (pin "9") (pinfunction "UART_RX_9") (pintype "input"))
    )
    (net (code "81") (name "Net-(IC11-UART_TX)") (class "Default")
      (node (ref "FR36") (pin "2") (pinfunction "2_2") (pintype "passive"))
      (node (ref "IC11") (pin "10") (pinfunction "UART_TX_10") (pintype "output"))
    )
    (net (code "82") (name "Net-(LED1-C)") (class "Default")
      (node (ref "LED1") (pin "K") (pinfunction "C_K") (pintype "power_in"))
      (node (ref "R137") (pin "1") (pinfunction "1_1") (pintype "passive"))
    )
    (net (code "83") (name "Net-(LED2-C)") (class "Default")
      (node (ref "LED2") (pin "K") (pinfunction "C_K") (pintype "power_in"))
      (node (ref "R142") (pin "1") (pinfunction "1_1") (pintype "passive"))
    )
    (net (code "84") (name "Net-(R141-Pad2)") (class "Default")
      (node (ref "R141") (pin "2") (pinfunction "2_2") (pintype "passive"))
      (node (ref "X8") (pin "37") (pinfunction "Reserved_37") (pintype "passive"))
    )
    (net (code "85") (name "Net-(R143-Pad2)") (class "Default")
      (node (ref "R143") (pin "2") (pinfunction "2_2") (pintype "passive"))
      (node (ref "X8") (pin "43") (pinfunction "Reserved_43") (pintype "passive"))
    )
    (net (code "86") (name "Net-(R144-Pad2)") (class "Default")
      (node (ref "R144") (pin "2") (pinfunction "2_2") (pintype "passive"))
      (node (ref "X8") (pin "45") (pinfunction "Reserved_45") (pintype "passive"))
    )
    (net (code "87") (name "Net-(X8-SMB_CLK)") (class "Default")
      (node (ref "R136") (pin "1") (pinfunction "1_1") (pintype "passive"))
      (node (ref "R140") (pin "1") (pinfunction "1_1") (pintype "passive"))
      (node (ref "X8") (pin "30") (pinfunction "SMB_CLK_30") (pintype "passive"))
    )
    (net (code "88") (name "Net-(X8-SMB_DATA)") (class "Default")
      (node (ref "R139") (pin "1") (pinfunction "1_1") (pintype "passive"))
      (node (ref "X8") (pin "32") (pinfunction "SMB_DATA_32") (pintype "passive"))
    )
    (net (code "89") (name "VCC1P8") (class "Default")
      (node (ref "C161") (pin "2") (pinfunction "2_2") (pintype "passive"))
      (node (ref "C163") (pin "2") (pinfunction "2_2") (pintype "passive"))
      (node (ref "C170") (pin "2") (pinfunction "2_2") (pintype "passive"))
      (node (ref "C172") (pin "2") (pinfunction "2_2") (pintype "passive"))
      (node (ref "IC10") (pin "14") (pinfunction "VCCA_14") (pintype "passive"))
      (node (ref "IC10") (pin "15") (pinfunction "DIR1_15") (pintype "passive"))
      (node (ref "IC10") (pin "5") (pinfunction "DIR3_5") (pintype "passive"))
      (node (ref "IC10") (pin "6") (pinfunction "DIR4_6") (pintype "passive"))
      (node (ref "IC12") (pin "14") (pinfunction "VCCA_14") (pintype "passive"))
      (node (ref "IC12") (pin "15") (pinfunction "DIR1_15") (pintype "passive"))
      (node (ref "IC12") (pin "16") (pinfunction "DIR2_16") (pintype "passive"))
      (node (ref "IC12") (pin "6") (pinfunction "DIR4_6") (pintype "passive"))
      (node (ref "IC13") (pin "14") (pinfunction "VCCA_14") (pintype "passive"))
      (node (ref "IC13") (pin "15") (pinfunction "DIR1_15") (pintype "passive"))
      (node (ref "IC13") (pin "16") (pinfunction "DIR2_16") (pintype "passive"))
      (node (ref "IC13") (pin "5") (pinfunction "DIR3_5") (pintype "passive"))
      (node (ref "IC13") (pin "6") (pinfunction "DIR4_6") (pintype "passive"))
      (node (ref "IC8") (pin "14") (pinfunction "VCCA_14") (pintype "passive"))
      (node (ref "IC8") (pin "15") (pinfunction "DIR1_15") (pintype "passive"))
      (node (ref "IC8") (pin "5") (pinfunction "DIR3_5") (pintype "passive"))
      (node (ref "R110") (pin "1") (pinfunction "1_1") (pintype "passive"))
      (node (ref "R111") (pin "1") (pinfunction "1_1") (pintype "passive"))
      (node (ref "R112") (pin "1") (pinfunction "1_1") (pintype "passive"))
      (node (ref "R113") (pin "1") (pinfunction "1_1") (pintype "passive"))
      (node (ref "R114") (pin "1") (pinfunction "1_1") (pintype "passive"))
      (node (ref "R115") (pin "1") (pinfunction "1_1") (pintype "passive"))
      (node (ref "R116") (pin "1") (pinfunction "1_1") (pintype "passive"))
      (node (ref "R117") (pin "1") (pinfunction "1_1") (pintype "passive"))
      (node (ref "R118") (pin "1") (pinfunction "1_1") (pintype "passive"))
      (node (ref "R119") (pin "1") (pinfunction "1_1") (pintype "passive"))
    )
    (net (code "90") (name "VCC3P3") (class "Default")
      (node (ref "C162") (pin "1") (pinfunction "1_1") (pintype "passive"))
      (node (ref "C164") (pin "1") (pinfunction "1_1") (pintype "passive"))
      (node (ref "C166") (pin "1") (pinfunction "1_1") (pintype "passive"))
      (node (ref "C171") (pin "1") (pinfunction "1_1") (pintype "passive"))
      (node (ref "C173") (pin "1") (pinfunction "1_1") (pintype "passive"))
      (node (ref "C177") (pin "1") (pinfunction "1_1") (pintype "passive"))
      (node (ref "C179") (pin "1") (pinfunction "1_1") (pintype "passive"))
      (node (ref "C180") (pin "1") (pinfunction "1_1") (pintype "passive"))
      (node (ref "FR37") (pin "1") (pinfunction "1_1") (pintype "passive"))
      (node (ref "IC10") (pin "13") (pinfunction "VCCB_13") (pintype "passive"))
      (node (ref "IC12") (pin "13") (pinfunction "VCCB_13") (pintype "passive"))
      (node (ref "IC13") (pin "13") (pinfunction "VCCB_13") (pintype "passive"))
      (node (ref "IC14") (pin "8") (pinfunction "VCC_8") (pintype "power_in"))
      (node (ref "IC15") (pin "5") (pinfunction "VDD_5") (pintype "power_in"))
      (node (ref "IC16") (pin "8") (pinfunction "VCC_8") (pintype "power_in"))
      (node (ref "IC8") (pin "13") (pinfunction "VCCB_13") (pintype "passive"))
      (node (ref "IC9") (pin "5") (pinfunction "V+_5") (pintype "power_in"))
      (node (ref "LED1") (pin "A") (pinfunction "A_A") (pintype "power_in"))
      (node (ref "LED2") (pin "A") (pinfunction "A_A") (pintype "power_in"))
      (node (ref "R130") (pin "1") (pinfunction "1_1") (pintype "passive"))
      (node (ref "X7") (pin "1") (pinfunction "1_1") (pintype "passive"))
    )
    (net (code "91") (name "VCC3P3_GNSS") (class "Default")
      (node (ref "C175") (pin "2") (pinfunction "2_2") (pintype "passive"))
      (node (ref "C176") (pin "2") (pinfunction "2_2") (pintype "passive"))
      (node (ref "FR37") (pin "2") (pinfunction "2_2") (pintype "passive"))
      (node (ref "IC11") (pin "14") (pinfunction "BV_14") (pintype "power_in"))
      (node (ref "IC11") (pin "15") (pinfunction "VCC_15") (pintype "power_in"))
      (node (ref "R108") (pin "2") (pinfunction "2_2") (pintype "passive"))
    )
    (net (code "92") (name "VCC3P3_MPCIE") (class "Default")
      (node (ref "R145") (pin "2") (pinfunction "2_2") (pintype "passive"))
      (node (ref "X8") (pin "2") (pinfunction "+3.3V_2") (pintype "passive"))
      (node (ref "X8") (pin "52") (pinfunction "+3.3V_52") (pintype "passive"))
    )
    (net (code "93") (name "unconnected-(IC9-ALERT-Pad3)") (class "Default")
      (node (ref "IC9") (pin "3") (pinfunction "ALERT_3") (pintype "output+no_connect"))
    )
    (net (code "94") (name "unconnected-(IC11-E2-Pad11)") (class "Default")
      (node (ref "IC11") (pin "11") (pinfunction "E2_11") (pintype "passive+no_connect"))
    )
    (net (code "95") (name "unconnected-(IC11-E3-Pad12)") (class "Default")
      (node (ref "IC11") (pin "12") (pinfunction "E3_12") (pintype "passive+no_connect"))
    )
    (net (code "96") (name "unconnected-(IC15-GPB5-Pad2)") (class "Default")
      (node (ref "IC15") (pin "2") (pinfunction "GPB5_2") (pintype "bidirectional+no_connect"))
    )
    (net (code "97") (name "unconnected-(IC15-INTA-Pad16)") (class "Default")
      (node (ref "IC15") (pin "16") (pinfunction "INTA_16") (pintype "open_collector+no_connect"))
    )
    (net (code "98") (name "unconnected-(IC15-INTB-Pad15)") (class "Default")
      (node (ref "IC15") (pin "15") (pinfunction "INTB_15") (pintype "open_collector+no_connect"))
    )
    (net (code "99") (name "unconnected-(IC15-NC-Pad7)") (class "Default")
      (node (ref "IC15") (pin "7") (pinfunction "NC_7") (pintype "passive+no_connect"))
    )
    (net (code "100") (name "unconnected-(IC15-NC-Pad10)") (class "Default")
      (node (ref "IC15") (pin "10") (pinfunction "NC_10") (pintype "passive+no_connect"))
    )
    (net (code "101") (name "unconnected-(IC16-NC-Pad1)") (class "Default")
      (node (ref "IC16") (pin "1") (pinfunction "NC_1") (pintype "passive+no_connect"))
    )
    (net (code "102") (name "unconnected-(IC16-NC-Pad2)") (class "Default")
      (node (ref "IC16") (pin "2") (pinfunction "NC_2") (pintype "passive+no_connect"))
    )
    (net (code "103") (name "unconnected-(IC16-NC-Pad3)") (class "Default")
      (node (ref "IC16") (pin "3") (pinfunction "NC_3") (pintype "passive+no_connect"))
    )
    (net (code "104") (name "unconnected-(IC16-NC-Pad7)") (class "Default")
      (node (ref "IC16") (pin "7") (pinfunction "NC_7") (pintype "passive+no_connect"))
    )
    (net (code "105") (name "unconnected-(X8-+1.5V-Pad6)") (class "Default")
      (node (ref "X8") (pin "6") (pinfunction "+1.5V_6") (pintype "passive+no_connect"))
    )
    (net (code "106") (name "unconnected-(X8-+1.5V-Pad28)") (class "Default")
      (node (ref "X8") (pin "28") (pinfunction "+1.5V_28") (pintype "passive+no_connect"))
    )
    (net (code "107") (name "unconnected-(X8-+1.5V-Pad48)") (class "Default")
      (node (ref "X8") (pin "48") (pinfunction "+1.5V_48") (pintype "passive+no_connect"))
    )
    (net (code "108") (name "unconnected-(X8-+3.3Vaux-Pad24)") (class "Default")
      (node (ref "X8") (pin "24") (pinfunction "+3.3Vaux_24") (pintype "passive+no_connect"))
    )
    (net (code "109") (name "unconnected-(X8-UIM_CLK-Pad12)") (class "Default")
      (node (ref "X8") (pin "12") (pinfunction "UIM_CLK_12") (pintype "passive+no_connect"))
    )
    (net (code "110") (name "unconnected-(X8-UIM_DATA-Pad10)") (class "Default")
      (node (ref "X8") (pin "10") (pinfunction "UIM_DATA_10") (pintype "passive+no_connect"))
    )
    (net (code "111") (name "unconnected-(X8-UIM_PWR-Pad8)") (class "Default")
      (node (ref "X8") (pin "8") (pinfunction "UIM_PWR_8") (pintype "passive+no_connect"))
    )
    (net (code "112") (name "unconnected-(X8-UIM_RESET-Pad14)") (class "Default")
      (node (ref "X8") (pin "14") (pinfunction "UIM_RESET_14") (pintype "passive+no_connect"))
    )
    (net (code "113") (name "unconnected-(X8-UIM_VPP-Pad16)") (class "Default")
      (node (ref "X8") (pin "16") (pinfunction "UIM_VPP_16") (pintype "passive+no_connect"))
    )
    (net (code "114") (name "unconnected-(X8-USB_DM-Pad36)") (class "Default")
      (node (ref "X8") (pin "36") (pinfunction "USB_DM_36") (pintype "passive+no_connect"))
    )
    (net (code "115") (name "unconnected-(X8-USB_DP-Pad38)") (class "Default")
      (node (ref "X8") (pin "38") (pinfunction "USB_DP_38") (pintype "passive+no_connect"))
    )
    (net (code "116") (name "unconnected-(X8-WAKE#-Pad1)") (class "Default")
      (node (ref "X8") (pin "1") (pinfunction "WAKE#_1") (pintype "passive+no_connect"))
    )
  )
)
